# wateralrm.net
KiCad netlist of a schematic drawn in EasyEDA
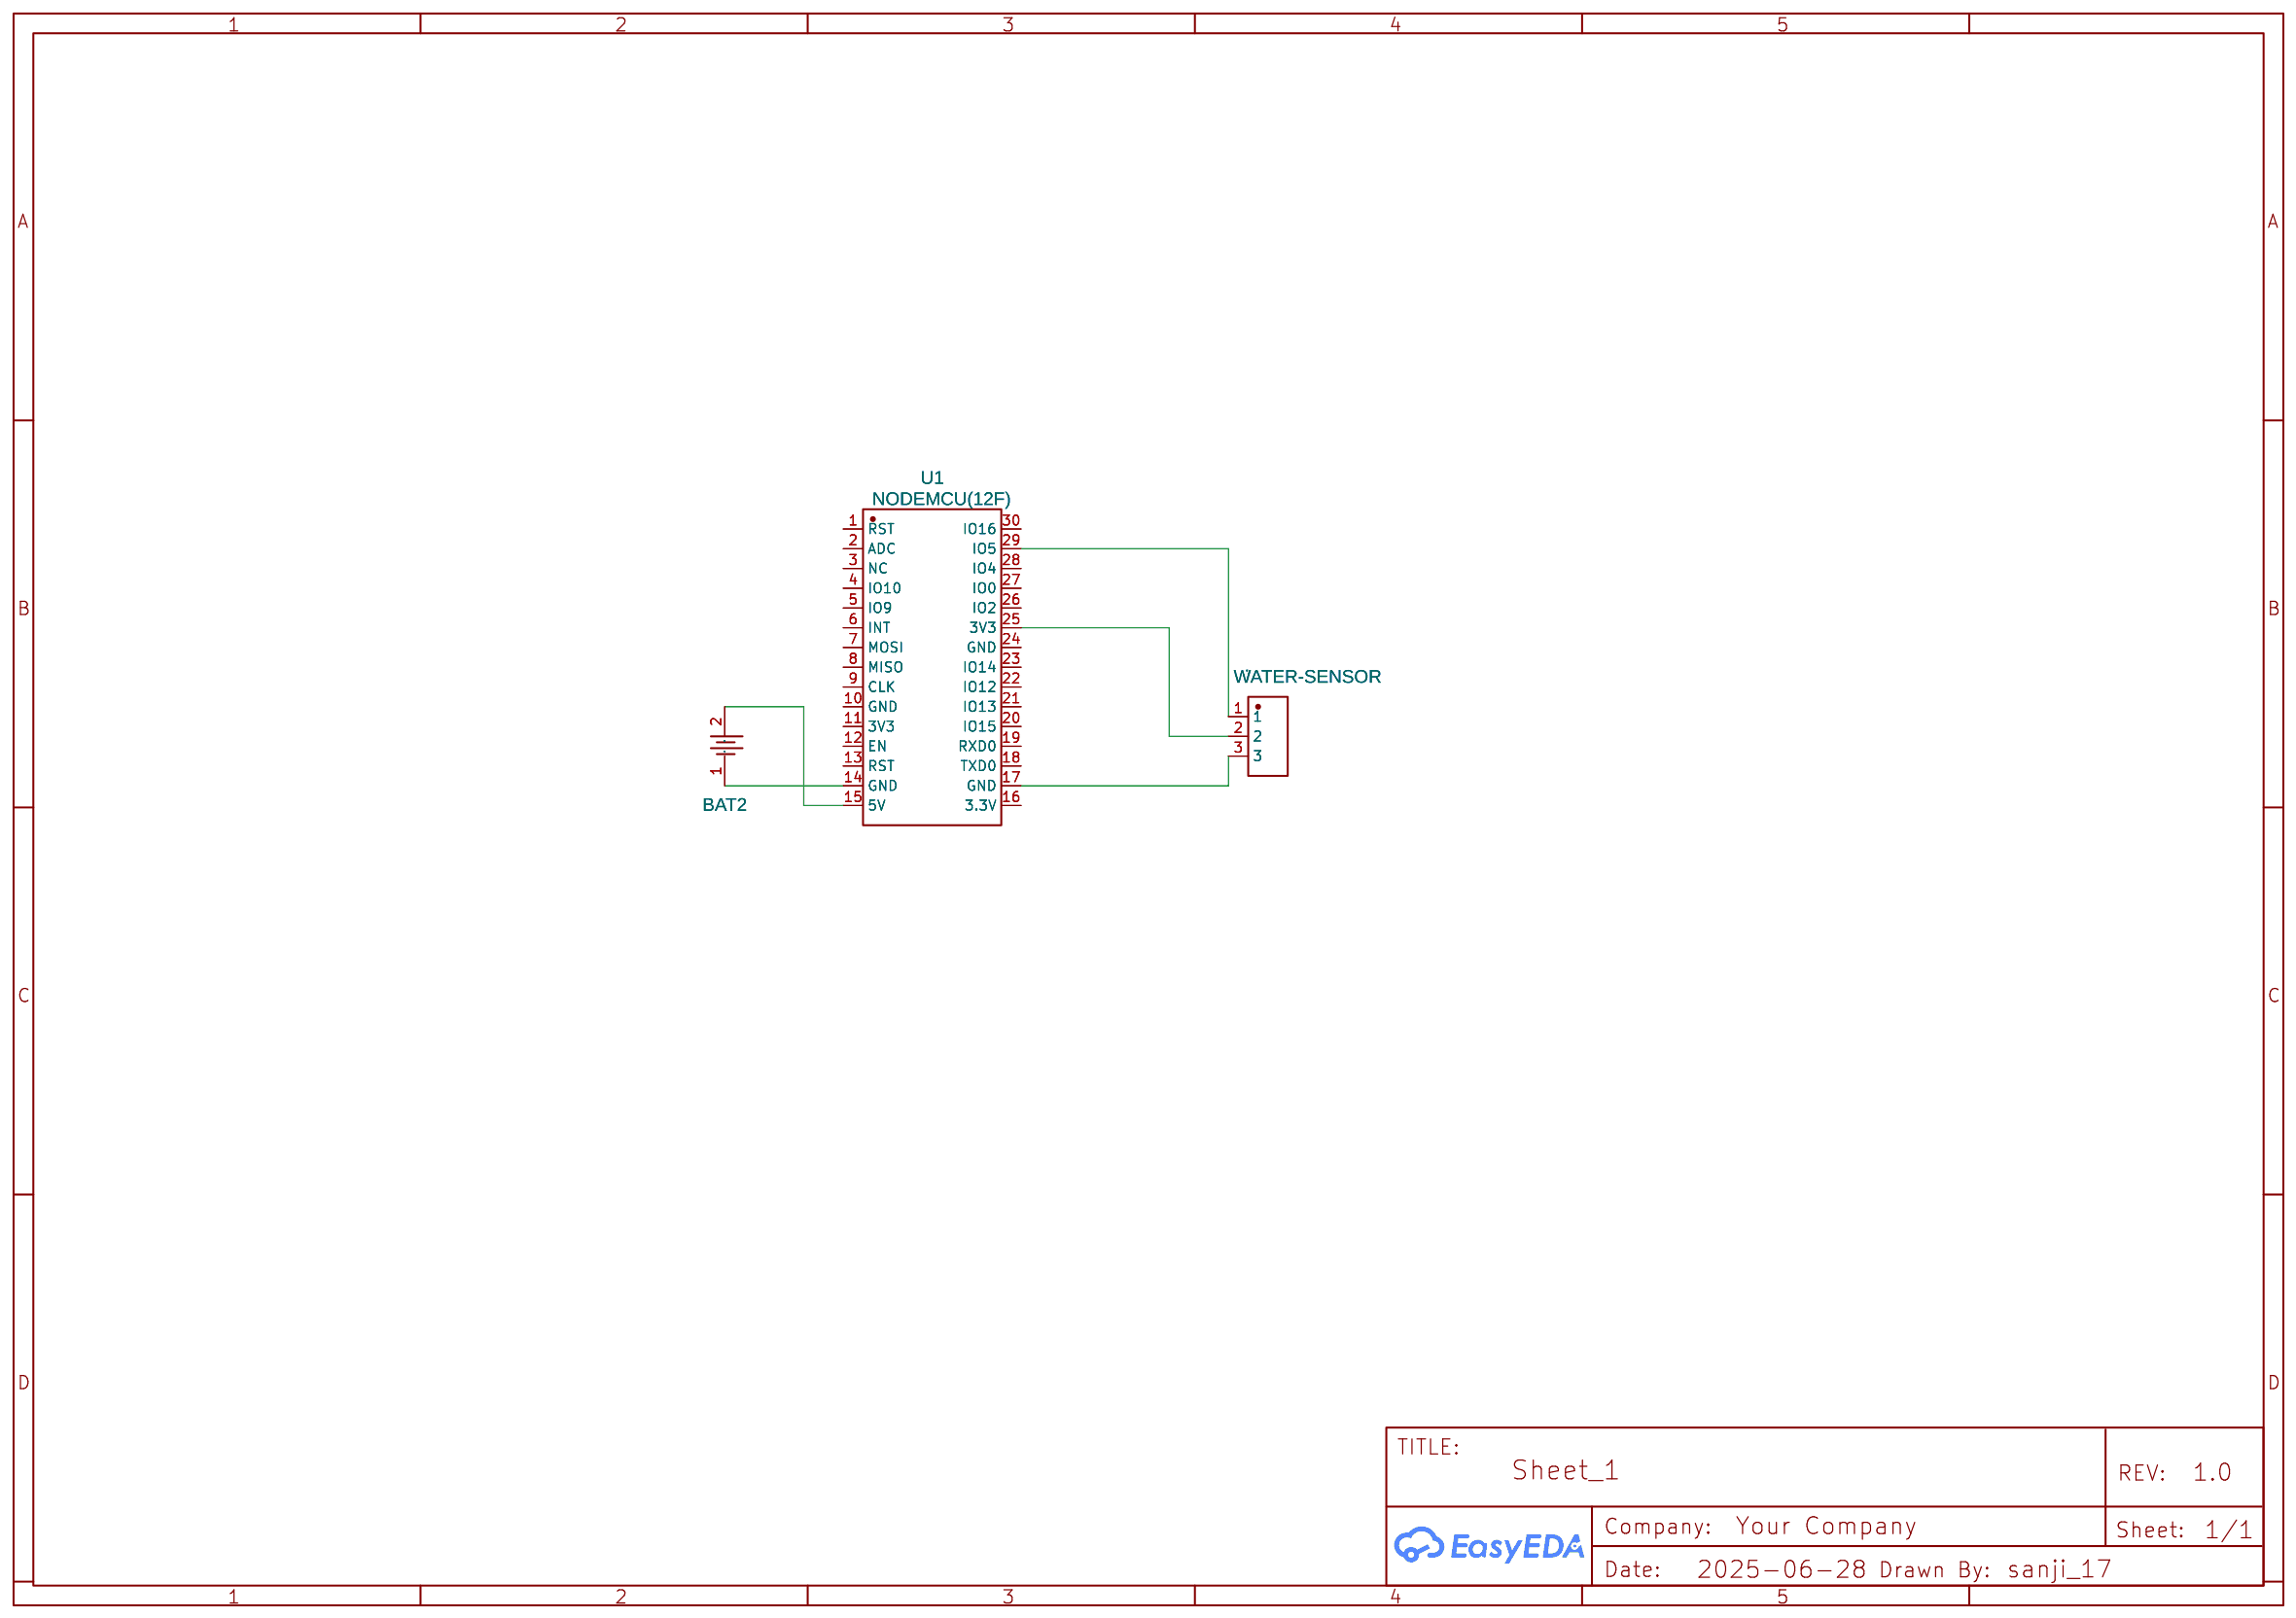
[diagram p0: schematic sheet]

(export (version "E")
  (design (tool "Eeschema 10.0.6"))
  (components
    (comp (ref ".")
      (value "WATER-SENSOR")
      (fields
        (field (name "Manufacturer Part") "HX PZ2.54-1x3P ZZ")
        (field (name "Manufacturer") "hanxia(韩下)")
      )
      (libsource (lib "") (part "HX PZ2.54-1X3P ZZ"))
    )
    (comp (ref "BAT2")
      (value "BH-18650-B6AA002")
      (fields (field (name "Manufacturer") "MYOUNG(美阳)"))
      (libsource (lib "") (part "BH-18650-B6AA002"))
    )
    (comp (ref "U1")
      (value "NODEMCU(12F)")
      (fields (field (name "Manufacturer") "Ai-Thinker(安信可)"))
      (libsource (lib "") (part "NODEMCU(12F)"))
    )
  )
  (nets
    (net (code "1") (name "Net-(.-Pad2)") (class "Default")
      (node (ref ".") (pin "2") (pinfunction "2_2") (pintype "unspecified"))
      (node (ref "U1") (pin "25") (pinfunction "3V3_25") (pintype "unspecified"))
    )
    (net (code "2") (name "Net-(.-Pad3)") (class "Default")
      (node (ref ".") (pin "3") (pinfunction "3_3") (pintype "unspecified"))
      (node (ref "U1") (pin "17") (pinfunction "GND_17") (pintype "unspecified"))
    )
    (net (code "3") (name "Net-(BAT2-Pad1)") (class "Default")
      (node (ref "BAT2") (pin "1") (pinfunction "1_1") (pintype "input"))
      (node (ref "U1") (pin "14") (pinfunction "GND_14") (pintype "unspecified"))
    )
    (net (code "4") (name "Net-(U1-5V)") (class "Default")
      (node (ref "BAT2") (pin "2") (pinfunction "2_2") (pintype "input"))
      (node (ref "U1") (pin "15") (pinfunction "5V_15") (pintype "unspecified"))
    )
    (net (code "5") (name "Net-(U1-IO5)") (class "Default")
      (node (ref ".") (pin "1") (pinfunction "1_1") (pintype "unspecified"))
      (node (ref "U1") (pin "29") (pinfunction "IO5_29") (pintype "unspecified"))
    )
    (net (code "6") (name "unconnected-(U1-3.3V-Pad16)") (class "Default")
      (node (ref "U1") (pin "16") (pinfunction "3.3V_16") (pintype "unspecified"))
    )
    (net (code "7") (name "unconnected-(U1-3V3-Pad11)") (class "Default")
      (node (ref "U1") (pin "11") (pinfunction "3V3_11") (pintype "unspecified"))
    )
    (net (code "8") (name "unconnected-(U1-ADC-Pad2)") (class "Default")
      (node (ref "U1") (pin "2") (pinfunction "ADC_2") (pintype "unspecified"))
    )
    (net (code "9") (name "unconnected-(U1-CLK-Pad9)") (class "Default")
      (node (ref "U1") (pin "9") (pinfunction "CLK_9") (pintype "unspecified"))
    )
    (net (code "10") (name "unconnected-(U1-EN-Pad12)") (class "Default")
      (node (ref "U1") (pin "12") (pinfunction "EN_12") (pintype "unspecified"))
    )
    (net (code "11") (name "unconnected-(U1-GND-Pad10)") (class "Default")
      (node (ref "U1") (pin "10") (pinfunction "GND_10") (pintype "unspecified"))
    )
    (net (code "12") (name "unconnected-(U1-GND-Pad24)") (class "Default")
      (node (ref "U1") (pin "24") (pinfunction "GND_24") (pintype "unspecified"))
    )
    (net (code "13") (name "unconnected-(U1-INT-Pad6)") (class "Default")
      (node (ref "U1") (pin "6") (pinfunction "INT_6") (pintype "unspecified"))
    )
    (net (code "14") (name "unconnected-(U1-IO0-Pad27)") (class "Default")
      (node (ref "U1") (pin "27") (pinfunction "IO0_27") (pintype "unspecified"))
    )
    (net (code "15") (name "unconnected-(U1-IO2-Pad26)") (class "Default")
      (node (ref "U1") (pin "26") (pinfunction "IO2_26") (pintype "unspecified"))
    )
    (net (code "16") (name "unconnected-(U1-IO4-Pad28)") (class "Default")
      (node (ref "U1") (pin "28") (pinfunction "IO4_28") (pintype "unspecified"))
    )
    (net (code "17") (name "unconnected-(U1-IO9-Pad5)") (class "Default")
      (node (ref "U1") (pin "5") (pinfunction "IO9_5") (pintype "unspecified"))
    )
    (net (code "18") (name "unconnected-(U1-IO10-Pad4)") (class "Default")
      (node (ref "U1") (pin "4") (pinfunction "IO10_4") (pintype "unspecified"))
    )
    (net (code "19") (name "unconnected-(U1-IO12-Pad22)") (class "Default")
      (node (ref "U1") (pin "22") (pinfunction "IO12_22") (pintype "unspecified"))
    )
    (net (code "20") (name "unconnected-(U1-IO13-Pad21)") (class "Default")
      (node (ref "U1") (pin "21") (pinfunction "IO13_21") (pintype "unspecified"))
    )
    (net (code "21") (name "unconnected-(U1-IO14-Pad23)") (class "Default")
      (node (ref "U1") (pin "23") (pinfunction "IO14_23") (pintype "unspecified"))
    )
    (net (code "22") (name "unconnected-(U1-IO15-Pad20)") (class "Default")
      (node (ref "U1") (pin "20") (pinfunction "IO15_20") (pintype "unspecified"))
    )
    (net (code "23") (name "unconnected-(U1-IO16-Pad30)") (class "Default")
      (node (ref "U1") (pin "30") (pinfunction "IO16_30") (pintype "unspecified"))
    )
    (net (code "24") (name "unconnected-(U1-MISO-Pad8)") (class "Default")
      (node (ref "U1") (pin "8") (pinfunction "MISO_8") (pintype "unspecified"))
    )
    (net (code "25") (name "unconnected-(U1-MOSI-Pad7)") (class "Default")
      (node (ref "U1") (pin "7") (pinfunction "MOSI_7") (pintype "unspecified"))
    )
    (net (code "26") (name "unconnected-(U1-NC-Pad3)") (class "Default")
      (node (ref "U1") (pin "3") (pinfunction "NC_3") (pintype "unspecified"))
    )
    (net (code "27") (name "unconnected-(U1-RST-Pad1)") (class "Default")
      (node (ref "U1") (pin "1") (pinfunction "RST_1") (pintype "unspecified"))
    )
    (net (code "28") (name "unconnected-(U1-RST-Pad13)") (class "Default")
      (node (ref "U1") (pin "13") (pinfunction "RST_13") (pintype "unspecified"))
    )
    (net (code "29") (name "unconnected-(U1-RXD0-Pad19)") (class "Default")
      (node (ref "U1") (pin "19") (pinfunction "RXD0_19") (pintype "unspecified"))
    )
    (net (code "30") (name "unconnected-(U1-TXD0-Pad18)") (class "Default")
      (node (ref "U1") (pin "18") (pinfunction "TXD0_18") (pintype "unspecified"))
    )
  )
)
